# simple-hat.net
KiCad netlist of a schematic drawn in EAGLE
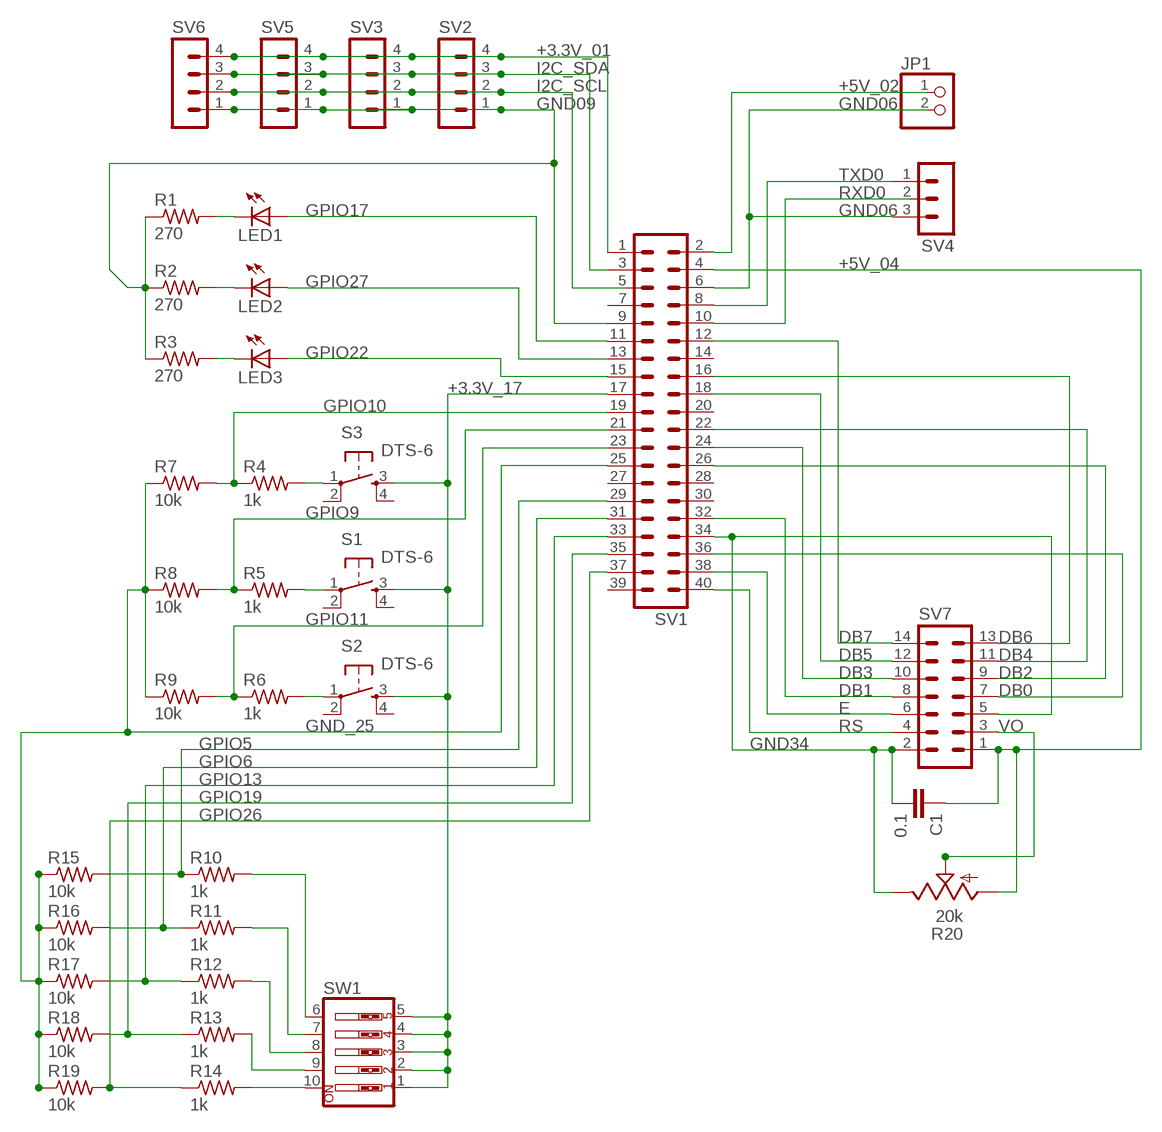
[diagram p0: schematic, sheet 1]

(export (version "E")
  (design (tool "Eeschema 10.0.6"))
  (components
    (comp (ref "C1")
      (value "0.1")
      (footprint "eagle-import:C050-025X075")
      (libsource (lib "eagle-import") (part "C-EU050-025X075"))
    )
    (comp (ref "JP1")
      (value "PINHD-1X2")
      (footprint "eagle-import:1X02")
      (libsource (lib "eagle-import") (part "PINHD-1X2"))
    )
    (comp (ref "LED1")
      (value "LED3MM")
      (footprint "eagle-import:LED3MM")
      (libsource (lib "eagle-import") (part "LED3MM"))
    )
    (comp (ref "LED2")
      (value "LED3MM")
      (footprint "eagle-import:LED3MM")
      (libsource (lib "eagle-import") (part "LED3MM"))
    )
    (comp (ref "LED3")
      (value "LED3MM")
      (footprint "eagle-import:LED3MM")
      (libsource (lib "eagle-import") (part "LED3MM"))
    )
    (comp (ref "R1")
      (value "270")
      (footprint "eagle-import:0207_7")
      (libsource (lib "eagle-import") (part "R-US_0207/7"))
    )
    (comp (ref "R2")
      (value "270")
      (footprint "eagle-import:0207_7")
      (libsource (lib "eagle-import") (part "R-US_0207/7"))
    )
    (comp (ref "R3")
      (value "270")
      (footprint "eagle-import:0207_7")
      (libsource (lib "eagle-import") (part "R-US_0207/7"))
    )
    (comp (ref "R4")
      (value "1k")
      (footprint "eagle-import:0207_7")
      (libsource (lib "eagle-import") (part "R-US_0207/7"))
    )
    (comp (ref "R5")
      (value "1k")
      (footprint "eagle-import:0207_7")
      (libsource (lib "eagle-import") (part "R-US_0207/7"))
    )
    (comp (ref "R6")
      (value "1k")
      (footprint "eagle-import:0207_7")
      (libsource (lib "eagle-import") (part "R-US_0207/7"))
    )
    (comp (ref "R7")
      (value "10k")
      (footprint "eagle-import:0207_7")
      (libsource (lib "eagle-import") (part "R-US_0207/7"))
    )
    (comp (ref "R8")
      (value "10k")
      (footprint "eagle-import:0207_7")
      (libsource (lib "eagle-import") (part "R-US_0207/7"))
    )
    (comp (ref "R9")
      (value "10k")
      (footprint "eagle-import:0207_7")
      (libsource (lib "eagle-import") (part "R-US_0207/7"))
    )
    (comp (ref "R10")
      (value "1k")
      (footprint "eagle-import:0207_7")
      (libsource (lib "eagle-import") (part "R-US_0207/7"))
    )
    (comp (ref "R11")
      (value "1k")
      (footprint "eagle-import:0207_7")
      (libsource (lib "eagle-import") (part "R-US_0207/7"))
    )
    (comp (ref "R12")
      (value "1k")
      (footprint "eagle-import:0207_7")
      (libsource (lib "eagle-import") (part "R-US_0207/7"))
    )
    (comp (ref "R13")
      (value "1k")
      (footprint "eagle-import:0207_7")
      (libsource (lib "eagle-import") (part "R-US_0207/7"))
    )
    (comp (ref "R14")
      (value "1k")
      (footprint "eagle-import:0207_7")
      (libsource (lib "eagle-import") (part "R-US_0207/7"))
    )
    (comp (ref "R15")
      (value "10k")
      (footprint "eagle-import:0207_7")
      (libsource (lib "eagle-import") (part "R-US_0207/7"))
    )
    (comp (ref "R16")
      (value "10k")
      (footprint "eagle-import:0207_7")
      (libsource (lib "eagle-import") (part "R-US_0207/7"))
    )
    (comp (ref "R17")
      (value "10k")
      (footprint "eagle-import:0207_7")
      (libsource (lib "eagle-import") (part "R-US_0207/7"))
    )
    (comp (ref "R18")
      (value "10k")
      (footprint "eagle-import:0207_7")
      (libsource (lib "eagle-import") (part "R-US_0207/7"))
    )
    (comp (ref "R19")
      (value "10k")
      (footprint "eagle-import:0207_7")
      (libsource (lib "eagle-import") (part "R-US_0207/7"))
    )
    (comp (ref "R20")
      (value "20k")
      (footprint "eagle-import:B25P")
      (libsource (lib "eagle-import") (part "TRIM_US-B25P"))
    )
    (comp (ref "S1")
      (value "DTS-6")
      (footprint "eagle-import:DTS-6")
      (libsource (lib "eagle-import") (part "DTS-6"))
    )
    (comp (ref "S2")
      (value "DTS-6")
      (footprint "eagle-import:DTS-6")
      (libsource (lib "eagle-import") (part "DTS-6"))
    )
    (comp (ref "S3")
      (value "DTS-6")
      (footprint "eagle-import:DTS-6")
      (libsource (lib "eagle-import") (part "DTS-6"))
    )
    (comp (ref "SV1")
      (value "MA20-2")
      (footprint "eagle-import:MA20-2")
      (libsource (lib "eagle-import") (part "MA20-2"))
    )
    (comp (ref "SV2")
      (value "MA04-1")
      (footprint "eagle-import:MA04-1")
      (libsource (lib "eagle-import") (part "MA04-1"))
    )
    (comp (ref "SV3")
      (value "MA04-1")
      (footprint "eagle-import:MA04-1")
      (libsource (lib "eagle-import") (part "MA04-1"))
    )
    (comp (ref "SV4")
      (value "MA03-1")
      (footprint "eagle-import:MA03-1")
      (libsource (lib "eagle-import") (part "MA03-1"))
    )
    (comp (ref "SV5")
      (value "MA04-1")
      (footprint "eagle-import:MA04-1")
      (libsource (lib "eagle-import") (part "MA04-1"))
    )
    (comp (ref "SV6")
      (value "MA04-1")
      (footprint "eagle-import:MA04-1")
      (libsource (lib "eagle-import") (part "MA04-1"))
    )
    (comp (ref "SV7")
      (value "MA07-2")
      (footprint "eagle-import:MA07-2")
      (libsource (lib "eagle-import") (part "MA07-2"))
    )
    (comp (ref "SW1")
      (value "SW_DIP-5")
      (footprint "eagle-import:EDG-05")
      (libsource (lib "eagle-import") (part "SW_DIP-5"))
    )
  )
  (nets
    (net (code "1") (name "/+3.3V_01") (class "Default")
      (node (ref "SV1") (pin "1") (pinfunction "1_1") (pintype "passive"))
      (node (ref "SV2") (pin "4") (pinfunction "4_4") (pintype "passive"))
      (node (ref "SV3") (pin "4") (pinfunction "4_4") (pintype "passive"))
      (node (ref "SV5") (pin "4") (pinfunction "4_4") (pintype "passive"))
      (node (ref "SV6") (pin "4") (pinfunction "4_4") (pintype "passive"))
    )
    (net (code "2") (name "/+3.3V_17") (class "Default")
      (node (ref "S1") (pin "3") (pinfunction "3_3") (pintype "passive"))
      (node (ref "S2") (pin "3") (pinfunction "3_3") (pintype "passive"))
      (node (ref "S3") (pin "3") (pinfunction "3_3") (pintype "passive"))
      (node (ref "SV1") (pin "17") (pinfunction "17_17") (pintype "passive"))
      (node (ref "SW1") (pin "1") (pinfunction "1_1") (pintype "passive"))
      (node (ref "SW1") (pin "2") (pinfunction "2_2") (pintype "passive"))
      (node (ref "SW1") (pin "3") (pinfunction "3_3") (pintype "passive"))
      (node (ref "SW1") (pin "4") (pinfunction "4_4") (pintype "passive"))
      (node (ref "SW1") (pin "5") (pinfunction "5_5") (pintype "passive"))
    )
    (net (code "3") (name "/+5V_02") (class "Default")
      (node (ref "JP1") (pin "1") (pinfunction "1_1") (pintype "passive"))
      (node (ref "SV1") (pin "2") (pinfunction "2_2") (pintype "passive"))
    )
    (net (code "4") (name "/+5V_04") (class "Default")
      (node (ref "C1") (pin "1") (pinfunction "1_1") (pintype "passive"))
      (node (ref "R20") (pin "A") (pinfunction "A_A") (pintype "passive"))
      (node (ref "SV1") (pin "4") (pinfunction "4_4") (pintype "passive"))
      (node (ref "SV7") (pin "1") (pinfunction "1_1") (pintype "passive"))
    )
    (net (code "5") (name "/DB0") (class "Default")
      (node (ref "SV1") (pin "36") (pinfunction "36_36") (pintype "passive"))
      (node (ref "SV7") (pin "7") (pinfunction "7_7") (pintype "passive"))
    )
    (net (code "6") (name "/DB1") (class "Default")
      (node (ref "SV1") (pin "32") (pinfunction "32_32") (pintype "passive"))
      (node (ref "SV7") (pin "8") (pinfunction "8_8") (pintype "passive"))
    )
    (net (code "7") (name "/DB2") (class "Default")
      (node (ref "SV1") (pin "26") (pinfunction "26_26") (pintype "passive"))
      (node (ref "SV7") (pin "9") (pinfunction "9_9") (pintype "passive"))
    )
    (net (code "8") (name "/DB3") (class "Default")
      (node (ref "SV1") (pin "24") (pinfunction "24_24") (pintype "passive"))
      (node (ref "SV7") (pin "10") (pinfunction "10_10") (pintype "passive"))
    )
    (net (code "9") (name "/DB4") (class "Default")
      (node (ref "SV1") (pin "22") (pinfunction "22_22") (pintype "passive"))
      (node (ref "SV7") (pin "11") (pinfunction "11_11") (pintype "passive"))
    )
    (net (code "10") (name "/DB5") (class "Default")
      (node (ref "SV1") (pin "18") (pinfunction "18_18") (pintype "passive"))
      (node (ref "SV7") (pin "12") (pinfunction "12_12") (pintype "passive"))
    )
    (net (code "11") (name "/DB6") (class "Default")
      (node (ref "SV1") (pin "16") (pinfunction "16_16") (pintype "passive"))
      (node (ref "SV7") (pin "13") (pinfunction "13_13") (pintype "passive"))
    )
    (net (code "12") (name "/DB7") (class "Default")
      (node (ref "SV1") (pin "12") (pinfunction "12_12") (pintype "passive"))
      (node (ref "SV7") (pin "14") (pinfunction "14_14") (pintype "passive"))
    )
    (net (code "13") (name "/E") (class "Default")
      (node (ref "SV1") (pin "38") (pinfunction "38_38") (pintype "passive"))
      (node (ref "SV7") (pin "6") (pinfunction "6_6") (pintype "passive"))
    )
    (net (code "14") (name "/GND06") (class "Default")
      (node (ref "JP1") (pin "2") (pinfunction "2_2") (pintype "passive"))
      (node (ref "SV1") (pin "6") (pinfunction "6_6") (pintype "passive"))
      (node (ref "SV4") (pin "3") (pinfunction "3_3") (pintype "passive"))
    )
    (net (code "15") (name "/GND09") (class "Default")
      (node (ref "R1") (pin "1") (pinfunction "1_1") (pintype "passive"))
      (node (ref "R2") (pin "1") (pinfunction "1_1") (pintype "passive"))
      (node (ref "R3") (pin "1") (pinfunction "1_1") (pintype "passive"))
      (node (ref "SV1") (pin "9") (pinfunction "9_9") (pintype "passive"))
      (node (ref "SV2") (pin "1") (pinfunction "1_1") (pintype "passive"))
      (node (ref "SV3") (pin "1") (pinfunction "1_1") (pintype "passive"))
      (node (ref "SV5") (pin "1") (pinfunction "1_1") (pintype "passive"))
      (node (ref "SV6") (pin "1") (pinfunction "1_1") (pintype "passive"))
    )
    (net (code "16") (name "/GND34") (class "Default")
      (node (ref "C1") (pin "2") (pinfunction "2_2") (pintype "passive"))
      (node (ref "R20") (pin "E") (pinfunction "E_E") (pintype "passive"))
      (node (ref "SV1") (pin "34") (pinfunction "34_34") (pintype "passive"))
      (node (ref "SV7") (pin "2") (pinfunction "2_2") (pintype "passive"))
      (node (ref "SV7") (pin "5") (pinfunction "5_5") (pintype "passive"))
    )
    (net (code "17") (name "/GND_25") (class "Default")
      (node (ref "R15") (pin "1") (pinfunction "1_1") (pintype "passive"))
      (node (ref "R16") (pin "1") (pinfunction "1_1") (pintype "passive"))
      (node (ref "R17") (pin "1") (pinfunction "1_1") (pintype "passive"))
      (node (ref "R18") (pin "1") (pinfunction "1_1") (pintype "passive"))
      (node (ref "R19") (pin "1") (pinfunction "1_1") (pintype "passive"))
      (node (ref "R7") (pin "1") (pinfunction "1_1") (pintype "passive"))
      (node (ref "R8") (pin "1") (pinfunction "1_1") (pintype "passive"))
      (node (ref "R9") (pin "1") (pinfunction "1_1") (pintype "passive"))
      (node (ref "SV1") (pin "25") (pinfunction "25_25") (pintype "passive"))
    )
    (net (code "18") (name "/GPIO5") (class "Default")
      (node (ref "R10") (pin "1") (pinfunction "1_1") (pintype "passive"))
      (node (ref "R15") (pin "2") (pinfunction "2_2") (pintype "passive"))
      (node (ref "SV1") (pin "29") (pinfunction "29_29") (pintype "passive"))
    )
    (net (code "19") (name "/GPIO6") (class "Default")
      (node (ref "R11") (pin "1") (pinfunction "1_1") (pintype "passive"))
      (node (ref "R16") (pin "2") (pinfunction "2_2") (pintype "passive"))
      (node (ref "SV1") (pin "31") (pinfunction "31_31") (pintype "passive"))
    )
    (net (code "20") (name "/GPIO9") (class "Default")
      (node (ref "R5") (pin "1") (pinfunction "1_1") (pintype "passive"))
      (node (ref "R8") (pin "2") (pinfunction "2_2") (pintype "passive"))
      (node (ref "SV1") (pin "21") (pinfunction "21_21") (pintype "passive"))
    )
    (net (code "21") (name "/GPIO10") (class "Default")
      (node (ref "R4") (pin "1") (pinfunction "1_1") (pintype "passive"))
      (node (ref "R7") (pin "2") (pinfunction "2_2") (pintype "passive"))
      (node (ref "SV1") (pin "19") (pinfunction "19_19") (pintype "passive"))
    )
    (net (code "22") (name "/GPIO11") (class "Default")
      (node (ref "R6") (pin "1") (pinfunction "1_1") (pintype "passive"))
      (node (ref "R9") (pin "2") (pinfunction "2_2") (pintype "passive"))
      (node (ref "SV1") (pin "23") (pinfunction "23_23") (pintype "passive"))
    )
    (net (code "23") (name "/GPIO13") (class "Default")
      (node (ref "R12") (pin "1") (pinfunction "1_1") (pintype "passive"))
      (node (ref "R17") (pin "2") (pinfunction "2_2") (pintype "passive"))
      (node (ref "SV1") (pin "33") (pinfunction "33_33") (pintype "passive"))
    )
    (net (code "24") (name "/GPIO17") (class "Default")
      (node (ref "LED1") (pin "A") (pinfunction "A_A") (pintype "passive"))
      (node (ref "SV1") (pin "11") (pinfunction "11_11") (pintype "passive"))
    )
    (net (code "25") (name "/GPIO19") (class "Default")
      (node (ref "R13") (pin "1") (pinfunction "1_1") (pintype "passive"))
      (node (ref "R18") (pin "2") (pinfunction "2_2") (pintype "passive"))
      (node (ref "SV1") (pin "35") (pinfunction "35_35") (pintype "passive"))
    )
    (net (code "26") (name "/GPIO22") (class "Default")
      (node (ref "LED3") (pin "A") (pinfunction "A_A") (pintype "passive"))
      (node (ref "SV1") (pin "15") (pinfunction "15_15") (pintype "passive"))
    )
    (net (code "27") (name "/GPIO26") (class "Default")
      (node (ref "R14") (pin "1") (pinfunction "1_1") (pintype "passive"))
      (node (ref "R19") (pin "2") (pinfunction "2_2") (pintype "passive"))
      (node (ref "SV1") (pin "37") (pinfunction "37_37") (pintype "passive"))
    )
    (net (code "28") (name "/GPIO27") (class "Default")
      (node (ref "LED2") (pin "A") (pinfunction "A_A") (pintype "passive"))
      (node (ref "SV1") (pin "13") (pinfunction "13_13") (pintype "passive"))
    )
    (net (code "29") (name "/I2C_SCL") (class "Default")
      (node (ref "SV2") (pin "2") (pinfunction "2_2") (pintype "passive"))
      (node (ref "SV3") (pin "2") (pinfunction "2_2") (pintype "passive"))
      (node (ref "SV5") (pin "2") (pinfunction "2_2") (pintype "passive"))
      (node (ref "SV6") (pin "2") (pinfunction "2_2") (pintype "passive"))
    )
    (net (code "30") (name "/I2C_SDA") (class "Default")
      (node (ref "SV1") (pin "3") (pinfunction "3_3") (pintype "passive"))
      (node (ref "SV2") (pin "3") (pinfunction "3_3") (pintype "passive"))
      (node (ref "SV3") (pin "3") (pinfunction "3_3") (pintype "passive"))
      (node (ref "SV5") (pin "3") (pinfunction "3_3") (pintype "passive"))
      (node (ref "SV6") (pin "3") (pinfunction "3_3") (pintype "passive"))
    )
    (net (code "31") (name "/RS") (class "Default")
      (node (ref "SV1") (pin "40") (pinfunction "40_40") (pintype "passive"))
      (node (ref "SV7") (pin "4") (pinfunction "4_4") (pintype "passive"))
    )
    (net (code "32") (name "/RXD0") (class "Default")
      (node (ref "SV1") (pin "10") (pinfunction "10_10") (pintype "passive"))
    )
    (net (code "33") (name "/TXD0") (class "Default")
      (node (ref "SV1") (pin "8") (pinfunction "8_8") (pintype "passive"))
      (node (ref "SV4") (pin "1") (pinfunction "1_1") (pintype "passive"))
    )
    (net (code "34") (name "/VO") (class "Default")
      (node (ref "R20") (pin "S") (pinfunction "S_S") (pintype "passive"))
      (node (ref "SV7") (pin "3") (pinfunction "3_3") (pintype "passive"))
    )
    (net (code "35") (name "Net-(LED1-C)") (class "Default")
      (node (ref "LED1") (pin "K") (pinfunction "C_K") (pintype "passive"))
      (node (ref "R1") (pin "2") (pinfunction "2_2") (pintype "passive"))
    )
    (net (code "36") (name "Net-(LED2-C)") (class "Default")
      (node (ref "LED2") (pin "K") (pinfunction "C_K") (pintype "passive"))
      (node (ref "R2") (pin "2") (pinfunction "2_2") (pintype "passive"))
    )
    (net (code "37") (name "Net-(LED3-C)") (class "Default")
      (node (ref "LED3") (pin "K") (pinfunction "C_K") (pintype "passive"))
      (node (ref "R3") (pin "2") (pinfunction "2_2") (pintype "passive"))
    )
    (net (code "38") (name "Net-(R4-Pad2)") (class "Default")
      (node (ref "R4") (pin "2") (pinfunction "2_2") (pintype "passive"))
      (node (ref "S3") (pin "1") (pinfunction "1_1") (pintype "passive"))
    )
    (net (code "39") (name "Net-(R5-Pad2)") (class "Default")
      (node (ref "R5") (pin "2") (pinfunction "2_2") (pintype "passive"))
      (node (ref "S1") (pin "1") (pinfunction "1_1") (pintype "passive"))
    )
    (net (code "40") (name "Net-(R6-Pad2)") (class "Default")
      (node (ref "R6") (pin "2") (pinfunction "2_2") (pintype "passive"))
      (node (ref "S2") (pin "1") (pinfunction "1_1") (pintype "passive"))
    )
    (net (code "41") (name "Net-(R10-Pad2)") (class "Default")
      (node (ref "R10") (pin "2") (pinfunction "2_2") (pintype "passive"))
      (node (ref "SW1") (pin "6") (pinfunction "6_6") (pintype "passive"))
    )
    (net (code "42") (name "Net-(R11-Pad2)") (class "Default")
      (node (ref "R11") (pin "2") (pinfunction "2_2") (pintype "passive"))
      (node (ref "SW1") (pin "7") (pinfunction "7_7") (pintype "passive"))
    )
    (net (code "43") (name "Net-(R12-Pad2)") (class "Default")
      (node (ref "R12") (pin "2") (pinfunction "2_2") (pintype "passive"))
      (node (ref "SW1") (pin "8") (pinfunction "8_8") (pintype "passive"))
    )
    (net (code "44") (name "Net-(R13-Pad2)") (class "Default")
      (node (ref "R13") (pin "2") (pinfunction "2_2") (pintype "passive"))
      (node (ref "SW1") (pin "9") (pinfunction "9_9") (pintype "passive"))
    )
    (net (code "45") (name "Net-(R14-Pad2)") (class "Default")
      (node (ref "R14") (pin "2") (pinfunction "2_2") (pintype "passive"))
      (node (ref "SW1") (pin "10") (pinfunction "10_10") (pintype "passive"))
    )
    (net (code "46") (name "unconnected-(S1-Pad2)") (class "Default")
      (node (ref "S1") (pin "2") (pinfunction "2_2") (pintype "passive"))
    )
    (net (code "47") (name "unconnected-(S1-Pad4)") (class "Default")
      (node (ref "S1") (pin "4") (pinfunction "4_4") (pintype "passive"))
    )
    (net (code "48") (name "unconnected-(S2-Pad2)") (class "Default")
      (node (ref "S2") (pin "2") (pinfunction "2_2") (pintype "passive"))
    )
    (net (code "49") (name "unconnected-(S2-Pad4)") (class "Default")
      (node (ref "S2") (pin "4") (pinfunction "4_4") (pintype "passive"))
    )
    (net (code "50") (name "unconnected-(S3-Pad2)") (class "Default")
      (node (ref "S3") (pin "2") (pinfunction "2_2") (pintype "passive"))
    )
    (net (code "51") (name "unconnected-(S3-Pad4)") (class "Default")
      (node (ref "S3") (pin "4") (pinfunction "4_4") (pintype "passive"))
    )
    (net (code "52") (name "unconnected-(SV1-Pad5)") (class "Default")
      (node (ref "SV1") (pin "5") (pinfunction "5_5") (pintype "passive"))
    )
    (net (code "53") (name "unconnected-(SV1-Pad7)") (class "Default")
      (node (ref "SV1") (pin "7") (pinfunction "7_7") (pintype "passive"))
    )
    (net (code "54") (name "unconnected-(SV1-Pad14)") (class "Default")
      (node (ref "SV1") (pin "14") (pinfunction "14_14") (pintype "passive"))
    )
    (net (code "55") (name "unconnected-(SV1-Pad20)") (class "Default")
      (node (ref "SV1") (pin "20") (pinfunction "20_20") (pintype "passive"))
    )
    (net (code "56") (name "unconnected-(SV1-Pad27)") (class "Default")
      (node (ref "SV1") (pin "27") (pinfunction "27_27") (pintype "passive"))
    )
    (net (code "57") (name "unconnected-(SV1-Pad28)") (class "Default")
      (node (ref "SV1") (pin "28") (pinfunction "28_28") (pintype "passive"))
    )
    (net (code "58") (name "unconnected-(SV1-Pad30)") (class "Default")
      (node (ref "SV1") (pin "30") (pinfunction "30_30") (pintype "passive"))
    )
    (net (code "59") (name "unconnected-(SV1-Pad39)") (class "Default")
      (node (ref "SV1") (pin "39") (pinfunction "39_39") (pintype "passive"))
    )
    (net (code "60") (name "unconnected-(SV4-Pad2)") (class "Default")
      (node (ref "SV4") (pin "2") (pinfunction "2_2") (pintype "passive"))
    )
  )
)
